# 02-MCU.net
KiCad netlist of a schematic drawn in Altium Designer
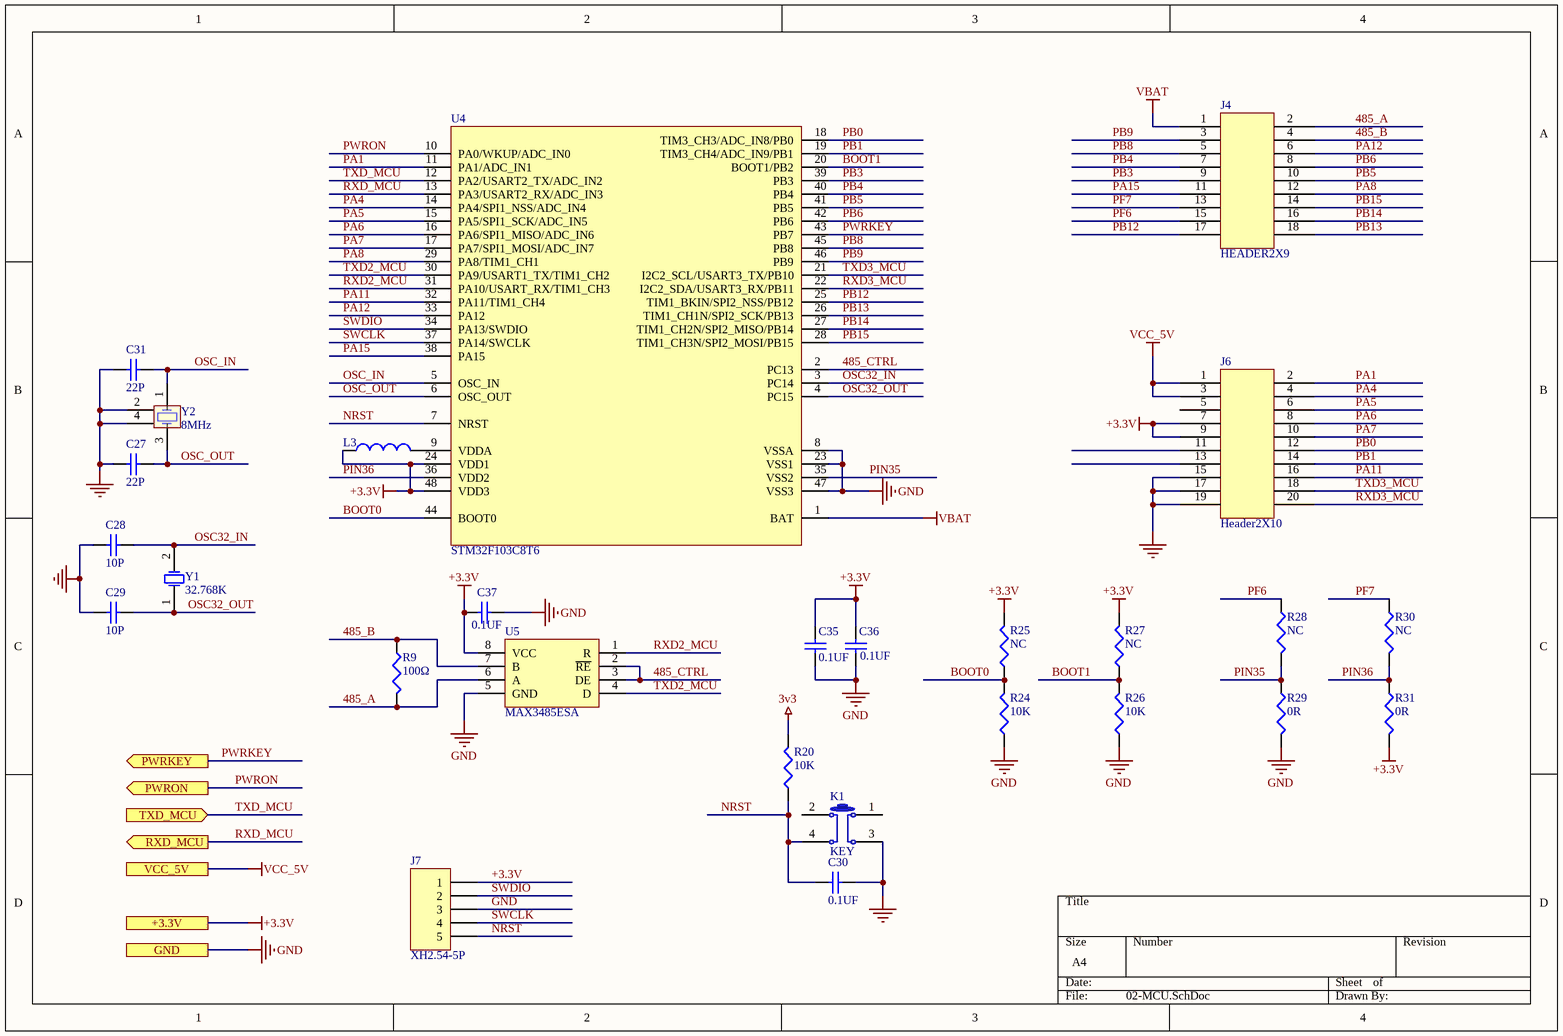
[diagram p0: 02-MCU.SchDoc]

(export (version "E")
  (design (tool "Eeschema 10.0.6"))
  (components
    (comp (ref "C27")
      (value "22P")
      (footprint "0603_C")
      (description "Capacitor")
      (fields (field (name "Comment") "Cap") (field (name "PUBLISHER") "Altium Limited"))
      (libsource (lib "Miscellaneous Devices") (part "Cap"))
    )
    (comp (ref "C28")
      (value "10P")
      (footprint "0603_C")
      (description "Capacitor")
      (fields (field (name "Comment") "Cap") (field (name "PUBLISHER") "Altium Limited"))
      (libsource (lib "Miscellaneous Devices") (part "Cap"))
    )
    (comp (ref "C29")
      (value "10P")
      (footprint "0603_C")
      (description "Capacitor")
      (fields (field (name "Comment") "Cap") (field (name "PUBLISHER") "Altium Limited"))
      (libsource (lib "Miscellaneous Devices") (part "Cap"))
    )
    (comp (ref "C30")
      (value "0.1UF")
      (footprint "0603_C")
      (description "Capacitor")
      (fields (field (name "Comment") "Cap") (field (name "PUBLISHER") "Altium Limited"))
      (libsource (lib "Miscellaneous Devices") (part "Cap"))
    )
    (comp (ref "C31")
      (value "22P")
      (footprint "0603_C")
      (description "Capacitor")
      (fields (field (name "Comment") "Cap") (field (name "PUBLISHER") "Altium Limited"))
      (libsource (lib "Miscellaneous Devices") (part "Cap"))
    )
    (comp (ref "C35")
      (value "0.1UF")
      (footprint "0603_C")
      (description "Capacitor")
      (fields (field (name "Comment") "Cap") (field (name "PUBLISHER") "Altium Limited"))
      (libsource (lib "Miscellaneous Devices") (part "Cap"))
    )
    (comp (ref "C36")
      (value "0.1UF")
      (footprint "0603_C")
      (description "Capacitor")
      (fields (field (name "Comment") "Cap") (field (name "PUBLISHER") "Altium Limited"))
      (libsource (lib "Miscellaneous Devices") (part "Cap"))
    )
    (comp (ref "C37")
      (value "0.1UF")
      (footprint "0603_C")
      (description "Capacitor")
      (fields (field (name "Comment") "Cap") (field (name "PUBLISHER") "Altium Limited"))
      (libsource (lib "Miscellaneous Devices") (part "Cap"))
    )
    (comp (ref "J4")
      (value "HEADER2X9")
      (footprint "DSP1.27-1.27-18")
      (libsource (lib "MySchlib") (part "HEADER2X9"))
    )
    (comp (ref "J6")
      (value "Header2X10")
      (footprint "DSP1.27-1.27-20")
      (libsource (lib "MySchlib") (part "Header2X10"))
    )
    (comp (ref "J7")
      (value "XH2.54-5P")
      (footprint "SIP5")
      (description "Header, 5-Pin, Right Angle")
      (fields (field (name "PUBLISHER") "Altium Limited"))
      (libsource (lib "Miscellaneous Connectors") (part "Header 5H"))
    )
    (comp (ref "K1") (value "KEY") (footprint "KEY_SMD5465") (libsource (lib "Schlib1") (part "KEY")))
    (comp (ref "L3")
      (value "Inductor")
      (footprint "0603_R")
      (fields (field (name "PUBLISHER") "Altium Limited"))
      (libsource (lib "Miscellaneous Devices") (part "Inductor"))
    )
    (comp (ref "R9") (value "100Ω") (footprint "0603_R") (libsource (lib "MySchlib") (part "RES1")))
    (comp (ref "R20")
      (value "10K")
      (footprint "0603_R")
      (description "Resistor")
      (fields (field (name "Comment") "Res3") (field (name "PUBLISHER") "Altium Limited"))
      (libsource (lib "Miscellaneous Devices") (part "Res3"))
    )
    (comp (ref "R24")
      (value "10K")
      (footprint "0603_R")
      (description "Resistor")
      (fields (field (name "Comment") "Res3") (field (name "PUBLISHER") "Altium Limited"))
      (libsource (lib "Miscellaneous Devices") (part "Res3"))
    )
    (comp (ref "R25")
      (value "NC")
      (footprint "0603_R")
      (description "Resistor")
      (fields (field (name "Comment") "Res3") (field (name "PUBLISHER") "Altium Limited"))
      (libsource (lib "Miscellaneous Devices") (part "Res3"))
    )
    (comp (ref "R26")
      (value "10K")
      (footprint "0603_R")
      (description "Resistor")
      (fields (field (name "Comment") "Res3") (field (name "PUBLISHER") "Altium Limited"))
      (libsource (lib "Miscellaneous Devices") (part "Res3"))
    )
    (comp (ref "R27")
      (value "NC")
      (footprint "0603_R")
      (description "Resistor")
      (fields (field (name "Comment") "Res3") (field (name "PUBLISHER") "Altium Limited"))
      (libsource (lib "Miscellaneous Devices") (part "Res3"))
    )
    (comp (ref "R28")
      (value "NC")
      (footprint "0603_R")
      (description "Resistor")
      (fields (field (name "Comment") "Res3") (field (name "PUBLISHER") "Altium Limited"))
      (libsource (lib "Miscellaneous Devices") (part "Res3"))
    )
    (comp (ref "R29")
      (value "0R")
      (footprint "0603_R")
      (description "Resistor")
      (fields (field (name "Comment") "Res3") (field (name "PUBLISHER") "Altium Limited"))
      (libsource (lib "Miscellaneous Devices") (part "Res3"))
    )
    (comp (ref "R30")
      (value "NC")
      (footprint "0603_R")
      (description "Resistor")
      (fields (field (name "Comment") "Res3") (field (name "PUBLISHER") "Altium Limited"))
      (libsource (lib "Miscellaneous Devices") (part "Res3"))
    )
    (comp (ref "R31")
      (value "0R")
      (footprint "0603_R")
      (description "Resistor")
      (fields (field (name "Comment") "Res3") (field (name "PUBLISHER") "Altium Limited"))
      (libsource (lib "Miscellaneous Devices") (part "Res3"))
    )
    (comp (ref "U4")
      (value "STM32F103C8T6")
      (footprint "LQFP48")
      (libsource (lib "MySchlib") (part "STM32F103C8T6"))
    )
    (comp (ref "U5") (value "MAX3485ESA") (footprint "SO8") (libsource (lib "MySchlib") (part "MAX485")))
    (comp (ref "Y1")
      (value "32.768K")
      (footprint "3215")
      (description "Crystal Oscillator")
      (fields (field (name "PUBLISHER") "Altium Limited"))
      (libsource (lib "Miscellaneous Devices") (part "XTAL"))
    )
    (comp (ref "Y2")
      (value "8MHz")
      (footprint "CRY_S3225")
      (description "CRYSTAL_S4_PASSIVE")
      (libsource (lib "EP_MCB_V4.1") (part "CRYSTAL_S4_1"))
    )
  )
  (nets
    (net (code "1") (name "+3.3V") (class "Default")
      (node (ref "C35") (pin "1") (pinfunction "1_1") (pintype "passive"))
      (node (ref "C36") (pin "1") (pinfunction "1_1") (pintype "passive"))
      (node (ref "C37") (pin "1") (pinfunction "1_1") (pintype "passive"))
      (node (ref "J6") (pin "7") (pinfunction "7_7") (pintype "passive"))
      (node (ref "J6") (pin "9") (pinfunction "9_9") (pintype "passive"))
      (node (ref "J7") (pin "1") (pinfunction "1_1") (pintype "passive"))
      (node (ref "L3") (pin "1") (pinfunction "1_1") (pintype "passive"))
      (node (ref "R25") (pin "2") (pinfunction "2_2") (pintype "passive"))
      (node (ref "R27") (pin "2") (pinfunction "2_2") (pintype "passive"))
      (node (ref "R31") (pin "2") (pinfunction "2_2") (pintype "passive"))
      (node (ref "U4") (pin "24") (pinfunction "VDD1_24") (pintype "passive"))
      (node (ref "U4") (pin "48") (pinfunction "VDD3_48") (pintype "passive"))
      (node (ref "U5") (pin "8") (pinfunction "VCC_8") (pintype "passive"))
    )
    (net (code "2") (name "/485_A") (class "Default")
      (node (ref "J4") (pin "2") (pinfunction "2_2") (pintype "passive"))
      (node (ref "R9") (pin "2") (pinfunction "2_2") (pintype "passive"))
      (node (ref "U5") (pin "6") (pinfunction "A_6") (pintype "passive"))
    )
    (net (code "3") (name "/485_B") (class "Default")
      (node (ref "J4") (pin "4") (pinfunction "4_4") (pintype "passive"))
      (node (ref "R9") (pin "1") (pinfunction "1_1") (pintype "passive"))
      (node (ref "U5") (pin "7") (pinfunction "B_7") (pintype "passive"))
    )
    (net (code "4") (name "/485_CTRL") (class "Default")
      (node (ref "U4") (pin "2") (pinfunction "PC13_2") (pintype "passive"))
      (node (ref "U5") (pin "2") (pinfunction "~{RE}_2") (pintype "passive"))
      (node (ref "U5") (pin "3") (pinfunction "DE_3") (pintype "passive"))
    )
    (net (code "5") (name "/BOOT0") (class "Default")
      (node (ref "R24") (pin "2") (pinfunction "2_2") (pintype "passive"))
      (node (ref "R25") (pin "1") (pinfunction "1_1") (pintype "passive"))
      (node (ref "U4") (pin "44") (pinfunction "BOOT0_44") (pintype "passive"))
    )
    (net (code "6") (name "/BOOT1") (class "Default")
      (node (ref "R26") (pin "2") (pinfunction "2_2") (pintype "passive"))
      (node (ref "R27") (pin "1") (pinfunction "1_1") (pintype "passive"))
      (node (ref "U4") (pin "20") (pinfunction "BOOT1/PB2_20") (pintype "passive"))
    )
    (net (code "7") (name "/NRST") (class "Default")
      (node (ref "C30") (pin "2") (pinfunction "2_2") (pintype "passive"))
      (node (ref "J7") (pin "5") (pinfunction "5_5") (pintype "passive"))
      (node (ref "K1") (pin "4") (pinfunction "4_4") (pintype "passive"))
      (node (ref "R20") (pin "1") (pinfunction "1_1") (pintype "passive"))
      (node (ref "U4") (pin "7") (pinfunction "NRST_7") (pintype "passive"))
    )
    (net (code "8") (name "/OSC32_IN") (class "Default")
      (node (ref "C28") (pin "1") (pinfunction "1_1") (pintype "passive"))
      (node (ref "U4") (pin "3") (pinfunction "PC14_3") (pintype "passive"))
      (node (ref "Y1") (pin "2") (pinfunction "OSC2_2") (pintype "passive"))
    )
    (net (code "9") (name "/OSC32_OUT") (class "Default")
      (node (ref "C29") (pin "1") (pinfunction "1_1") (pintype "passive"))
      (node (ref "U4") (pin "4") (pinfunction "PC15_4") (pintype "passive"))
      (node (ref "Y1") (pin "1") (pinfunction "OSC1_1") (pintype "passive"))
    )
    (net (code "10") (name "/OSC_IN") (class "Default")
      (node (ref "C31") (pin "1") (pinfunction "1_1") (pintype "passive"))
      (node (ref "U4") (pin "5") (pinfunction "OSC_IN_5") (pintype "passive"))
      (node (ref "Y2") (pin "1") (pinfunction "1_1") (pintype "passive"))
    )
    (net (code "11") (name "/OSC_OUT") (class "Default")
      (node (ref "C27") (pin "1") (pinfunction "1_1") (pintype "passive"))
      (node (ref "U4") (pin "6") (pinfunction "OSC_OUT_6") (pintype "passive"))
      (node (ref "Y2") (pin "3") (pinfunction "3_3") (pintype "passive"))
    )
    (net (code "12") (name "/PA1") (class "Default")
      (node (ref "J6") (pin "2") (pinfunction "2_2") (pintype "passive"))
      (node (ref "U4") (pin "11") (pinfunction "PA1/ADC_IN1_11") (pintype "passive"))
    )
    (net (code "13") (name "/PA4") (class "Default")
      (node (ref "J6") (pin "4") (pinfunction "4_4") (pintype "passive"))
      (node (ref "U4") (pin "14") (pinfunction "PA4/SPI1_NSS/ADC_IN4_14") (pintype "passive"))
    )
    (net (code "14") (name "/PA5") (class "Default")
      (node (ref "J6") (pin "6") (pinfunction "6_6") (pintype "passive"))
      (node (ref "U4") (pin "15") (pinfunction "PA5/SPI1_SCK/ADC_IN5_15") (pintype "passive"))
    )
    (net (code "15") (name "/PA6") (class "Default")
      (node (ref "J6") (pin "8") (pinfunction "8_8") (pintype "passive"))
      (node (ref "U4") (pin "16") (pinfunction "PA6/SPI1_MISO/ADC_IN6_16") (pintype "passive"))
    )
    (net (code "16") (name "/PA7") (class "Default")
      (node (ref "J6") (pin "10") (pinfunction "10_10") (pintype "passive"))
      (node (ref "U4") (pin "17") (pinfunction "PA7/SPI1_MOSI/ADC_IN7_17") (pintype "passive"))
    )
    (net (code "17") (name "/PA8") (class "Default")
      (node (ref "J4") (pin "12") (pinfunction "12_12") (pintype "passive"))
      (node (ref "U4") (pin "29") (pinfunction "PA8/TIM1_CH1_29") (pintype "passive"))
    )
    (net (code "18") (name "/PA11") (class "Default")
      (node (ref "J6") (pin "16") (pinfunction "16_16") (pintype "passive"))
      (node (ref "U4") (pin "32") (pinfunction "PA11/TIM1_CH4_32") (pintype "passive"))
    )
    (net (code "19") (name "/PA12") (class "Default")
      (node (ref "J4") (pin "6") (pinfunction "6_6") (pintype "passive"))
      (node (ref "U4") (pin "33") (pinfunction "PA12_33") (pintype "passive"))
    )
    (net (code "20") (name "/PA15") (class "Default")
      (node (ref "J4") (pin "11") (pinfunction "11_11") (pintype "passive"))
      (node (ref "U4") (pin "38") (pinfunction "PA15_38") (pintype "passive"))
    )
    (net (code "21") (name "/PB0") (class "Default")
      (node (ref "J6") (pin "12") (pinfunction "12_12") (pintype "passive"))
      (node (ref "U4") (pin "18") (pinfunction "TIM3_CH3/ADC_IN8/PB0_18") (pintype "passive"))
    )
    (net (code "22") (name "/PB1") (class "Default")
      (node (ref "J6") (pin "14") (pinfunction "14_14") (pintype "passive"))
      (node (ref "U4") (pin "19") (pinfunction "TIM3_CH4/ADC_IN9/PB1_19") (pintype "passive"))
    )
    (net (code "23") (name "/PB3") (class "Default")
      (node (ref "J4") (pin "9") (pinfunction "9_9") (pintype "passive"))
      (node (ref "U4") (pin "39") (pinfunction "PB3_39") (pintype "passive"))
    )
    (net (code "24") (name "/PB4") (class "Default")
      (node (ref "J4") (pin "7") (pinfunction "7_7") (pintype "passive"))
      (node (ref "U4") (pin "40") (pinfunction "PB4_40") (pintype "passive"))
    )
    (net (code "25") (name "/PB5") (class "Default")
      (node (ref "J4") (pin "10") (pinfunction "10_10") (pintype "passive"))
      (node (ref "U4") (pin "41") (pinfunction "PB5_41") (pintype "passive"))
    )
    (net (code "26") (name "/PB6") (class "Default")
      (node (ref "J4") (pin "8") (pinfunction "8_8") (pintype "passive"))
      (node (ref "U4") (pin "42") (pinfunction "PB6_42") (pintype "passive"))
    )
    (net (code "27") (name "/PB8") (class "Default")
      (node (ref "J4") (pin "5") (pinfunction "5_5") (pintype "passive"))
      (node (ref "U4") (pin "45") (pinfunction "PB8_45") (pintype "passive"))
    )
    (net (code "28") (name "/PB9") (class "Default")
      (node (ref "J4") (pin "3") (pinfunction "3_3") (pintype "passive"))
      (node (ref "U4") (pin "46") (pinfunction "PB9_46") (pintype "passive"))
    )
    (net (code "29") (name "/PB12") (class "Default")
      (node (ref "J4") (pin "17") (pinfunction "17_17") (pintype "passive"))
      (node (ref "U4") (pin "25") (pinfunction "TIM1_BKIN/SPI2_NSS/PB12_25") (pintype "passive"))
    )
    (net (code "30") (name "/PB13") (class "Default")
      (node (ref "J4") (pin "18") (pinfunction "18_18") (pintype "passive"))
      (node (ref "U4") (pin "26") (pinfunction "TIM1_CH1N/SPI2_SCK/PB13_26") (pintype "passive"))
    )
    (net (code "31") (name "/PB14") (class "Default")
      (node (ref "J4") (pin "16") (pinfunction "16_16") (pintype "passive"))
      (node (ref "U4") (pin "27") (pinfunction "TIM1_CH2N/SPI2_MISO/PB14_27") (pintype "passive"))
    )
    (net (code "32") (name "/PB15") (class "Default")
      (node (ref "J4") (pin "14") (pinfunction "14_14") (pintype "passive"))
      (node (ref "U4") (pin "28") (pinfunction "TIM1_CH3N/SPI2_MOSI/PB15_28") (pintype "passive"))
    )
    (net (code "33") (name "/PF6") (class "Default")
      (node (ref "J4") (pin "15") (pinfunction "15_15") (pintype "passive"))
      (node (ref "R28") (pin "1") (pinfunction "1_1") (pintype "passive"))
    )
    (net (code "34") (name "/PF7") (class "Default")
      (node (ref "J4") (pin "13") (pinfunction "13_13") (pintype "passive"))
      (node (ref "R30") (pin "1") (pinfunction "1_1") (pintype "passive"))
    )
    (net (code "35") (name "/PIN35") (class "Default")
      (node (ref "R28") (pin "2") (pinfunction "2_2") (pintype "passive"))
      (node (ref "R29") (pin "1") (pinfunction "1_1") (pintype "passive"))
      (node (ref "U4") (pin "35") (pinfunction "VSS2_35") (pintype "passive"))
    )
    (net (code "36") (name "/PIN36") (class "Default")
      (node (ref "R30") (pin "2") (pinfunction "2_2") (pintype "passive"))
      (node (ref "R31") (pin "1") (pinfunction "1_1") (pintype "passive"))
      (node (ref "U4") (pin "36") (pinfunction "VDD2_36") (pintype "passive"))
    )
    (net (code "37") (name "/PWRKEY") (class "Default")
      (node (ref "U4") (pin "43") (pinfunction "PB7_43") (pintype "passive"))
    )
    (net (code "38") (name "/PWRON") (class "Default")
      (node (ref "U4") (pin "10") (pinfunction "PA0/WKUP/ADC_IN0_10") (pintype "passive"))
    )
    (net (code "39") (name "/RXD2_MCU") (class "Default")
      (node (ref "U4") (pin "31") (pinfunction "PA10/USART_RX/TIM1_CH3_31") (pintype "passive"))
      (node (ref "U5") (pin "1") (pinfunction "R_1") (pintype "passive"))
    )
    (net (code "40") (name "/RXD3_MCU") (class "Default")
      (node (ref "J6") (pin "20") (pinfunction "20_20") (pintype "passive"))
      (node (ref "U4") (pin "22") (pinfunction "I2C2_SDA/USART3_RX/PB11_22") (pintype "passive"))
    )
    (net (code "41") (name "/RXD_MCU") (class "Default")
      (node (ref "U4") (pin "13") (pinfunction "PA3/USART2_RX/ADC_IN3_13") (pintype "passive"))
    )
    (net (code "42") (name "/SWCLK") (class "Default")
      (node (ref "J7") (pin "4") (pinfunction "4_4") (pintype "passive"))
      (node (ref "U4") (pin "37") (pinfunction "PA14/SWCLK_37") (pintype "passive"))
    )
    (net (code "43") (name "/SWDIO") (class "Default")
      (node (ref "J7") (pin "2") (pinfunction "2_2") (pintype "passive"))
      (node (ref "U4") (pin "34") (pinfunction "PA13/SWDIO_34") (pintype "passive"))
    )
    (net (code "44") (name "/TXD2_MCU") (class "Default")
      (node (ref "U4") (pin "30") (pinfunction "PA9/USART1_TX/TIM1_CH2_30") (pintype "passive"))
      (node (ref "U5") (pin "4") (pinfunction "D_4") (pintype "passive"))
    )
    (net (code "45") (name "/TXD3_MCU") (class "Default")
      (node (ref "J6") (pin "18") (pinfunction "18_18") (pintype "passive"))
      (node (ref "U4") (pin "21") (pinfunction "I2C2_SCL/USART3_TX/PB10_21") (pintype "passive"))
    )
    (net (code "46") (name "/TXD_MCU") (class "Default")
      (node (ref "U4") (pin "12") (pinfunction "PA2/USART2_TX/ADC_IN2_12") (pintype "passive"))
    )
    (net (code "47") (name "3v3") (class "Default")
      (node (ref "R20") (pin "2") (pinfunction "2_2") (pintype "passive"))
    )
    (net (code "48") (name "GND") (class "Default")
      (node (ref "C27") (pin "2") (pinfunction "2_2") (pintype "passive"))
      (node (ref "C28") (pin "2") (pinfunction "2_2") (pintype "passive"))
      (node (ref "C29") (pin "2") (pinfunction "2_2") (pintype "passive"))
      (node (ref "C30") (pin "1") (pinfunction "1_1") (pintype "passive"))
      (node (ref "C31") (pin "2") (pinfunction "2_2") (pintype "passive"))
      (node (ref "C35") (pin "2") (pinfunction "2_2") (pintype "passive"))
      (node (ref "C36") (pin "2") (pinfunction "2_2") (pintype "passive"))
      (node (ref "C37") (pin "2") (pinfunction "2_2") (pintype "passive"))
      (node (ref "J6") (pin "15") (pinfunction "15_15") (pintype "passive"))
      (node (ref "J6") (pin "17") (pinfunction "17_17") (pintype "passive"))
      (node (ref "J6") (pin "19") (pinfunction "19_19") (pintype "passive"))
      (node (ref "J7") (pin "3") (pinfunction "3_3") (pintype "passive"))
      (node (ref "K1") (pin "3") (pinfunction "3_3") (pintype "passive"))
      (node (ref "R24") (pin "1") (pinfunction "1_1") (pintype "passive"))
      (node (ref "R26") (pin "1") (pinfunction "1_1") (pintype "passive"))
      (node (ref "R29") (pin "2") (pinfunction "2_2") (pintype "passive"))
      (node (ref "U4") (pin "23") (pinfunction "VSS1_23") (pintype "passive"))
      (node (ref "U4") (pin "47") (pinfunction "VSS3_47") (pintype "passive"))
      (node (ref "U4") (pin "8") (pinfunction "VSSA_8") (pintype "passive"))
      (node (ref "U5") (pin "5") (pinfunction "GND_5") (pintype "passive"))
      (node (ref "Y2") (pin "2") (pinfunction "2_2") (pintype "passive"))
      (node (ref "Y2") (pin "4") (pinfunction "4_4") (pintype "passive"))
    )
    (net (code "49") (name "Net-(U4-VDDA)") (class "Default")
      (node (ref "L3") (pin "2") (pinfunction "2_2") (pintype "passive"))
      (node (ref "U4") (pin "9") (pinfunction "VDDA_9") (pintype "passive"))
    )
    (net (code "50") (name "VBAT") (class "Default")
      (node (ref "J4") (pin "1") (pinfunction "1_1") (pintype "passive"))
      (node (ref "U4") (pin "1") (pinfunction "BAT_1") (pintype "passive"))
    )
    (net (code "51") (name "VCC_5V") (class "Default")
      (node (ref "J6") (pin "1") (pinfunction "1_1") (pintype "passive"))
      (node (ref "J6") (pin "3") (pinfunction "3_3") (pintype "passive"))
    )
    (net (code "52") (name "unconnected-(J6-Pad5)") (class "Default")
      (node (ref "J6") (pin "5") (pinfunction "5_5") (pintype "passive"))
    )
    (net (code "53") (name "unconnected-(J6-Pad11)") (class "Default")
      (node (ref "J6") (pin "11") (pinfunction "11_11") (pintype "passive"))
    )
    (net (code "54") (name "unconnected-(J6-Pad13)") (class "Default")
      (node (ref "J6") (pin "13") (pinfunction "13_13") (pintype "passive"))
    )
    (net (code "55") (name "unconnected-(K1-Pad1)") (class "Default")
      (node (ref "K1") (pin "1") (pinfunction "1_1") (pintype "passive"))
    )
    (net (code "56") (name "unconnected-(K1-Pad2)") (class "Default")
      (node (ref "K1") (pin "2") (pinfunction "2_2") (pintype "passive"))
    )
  )
)
